# 1_RK3399_PowerPins.net
KiCad netlist of a schematic drawn in Altium Designer
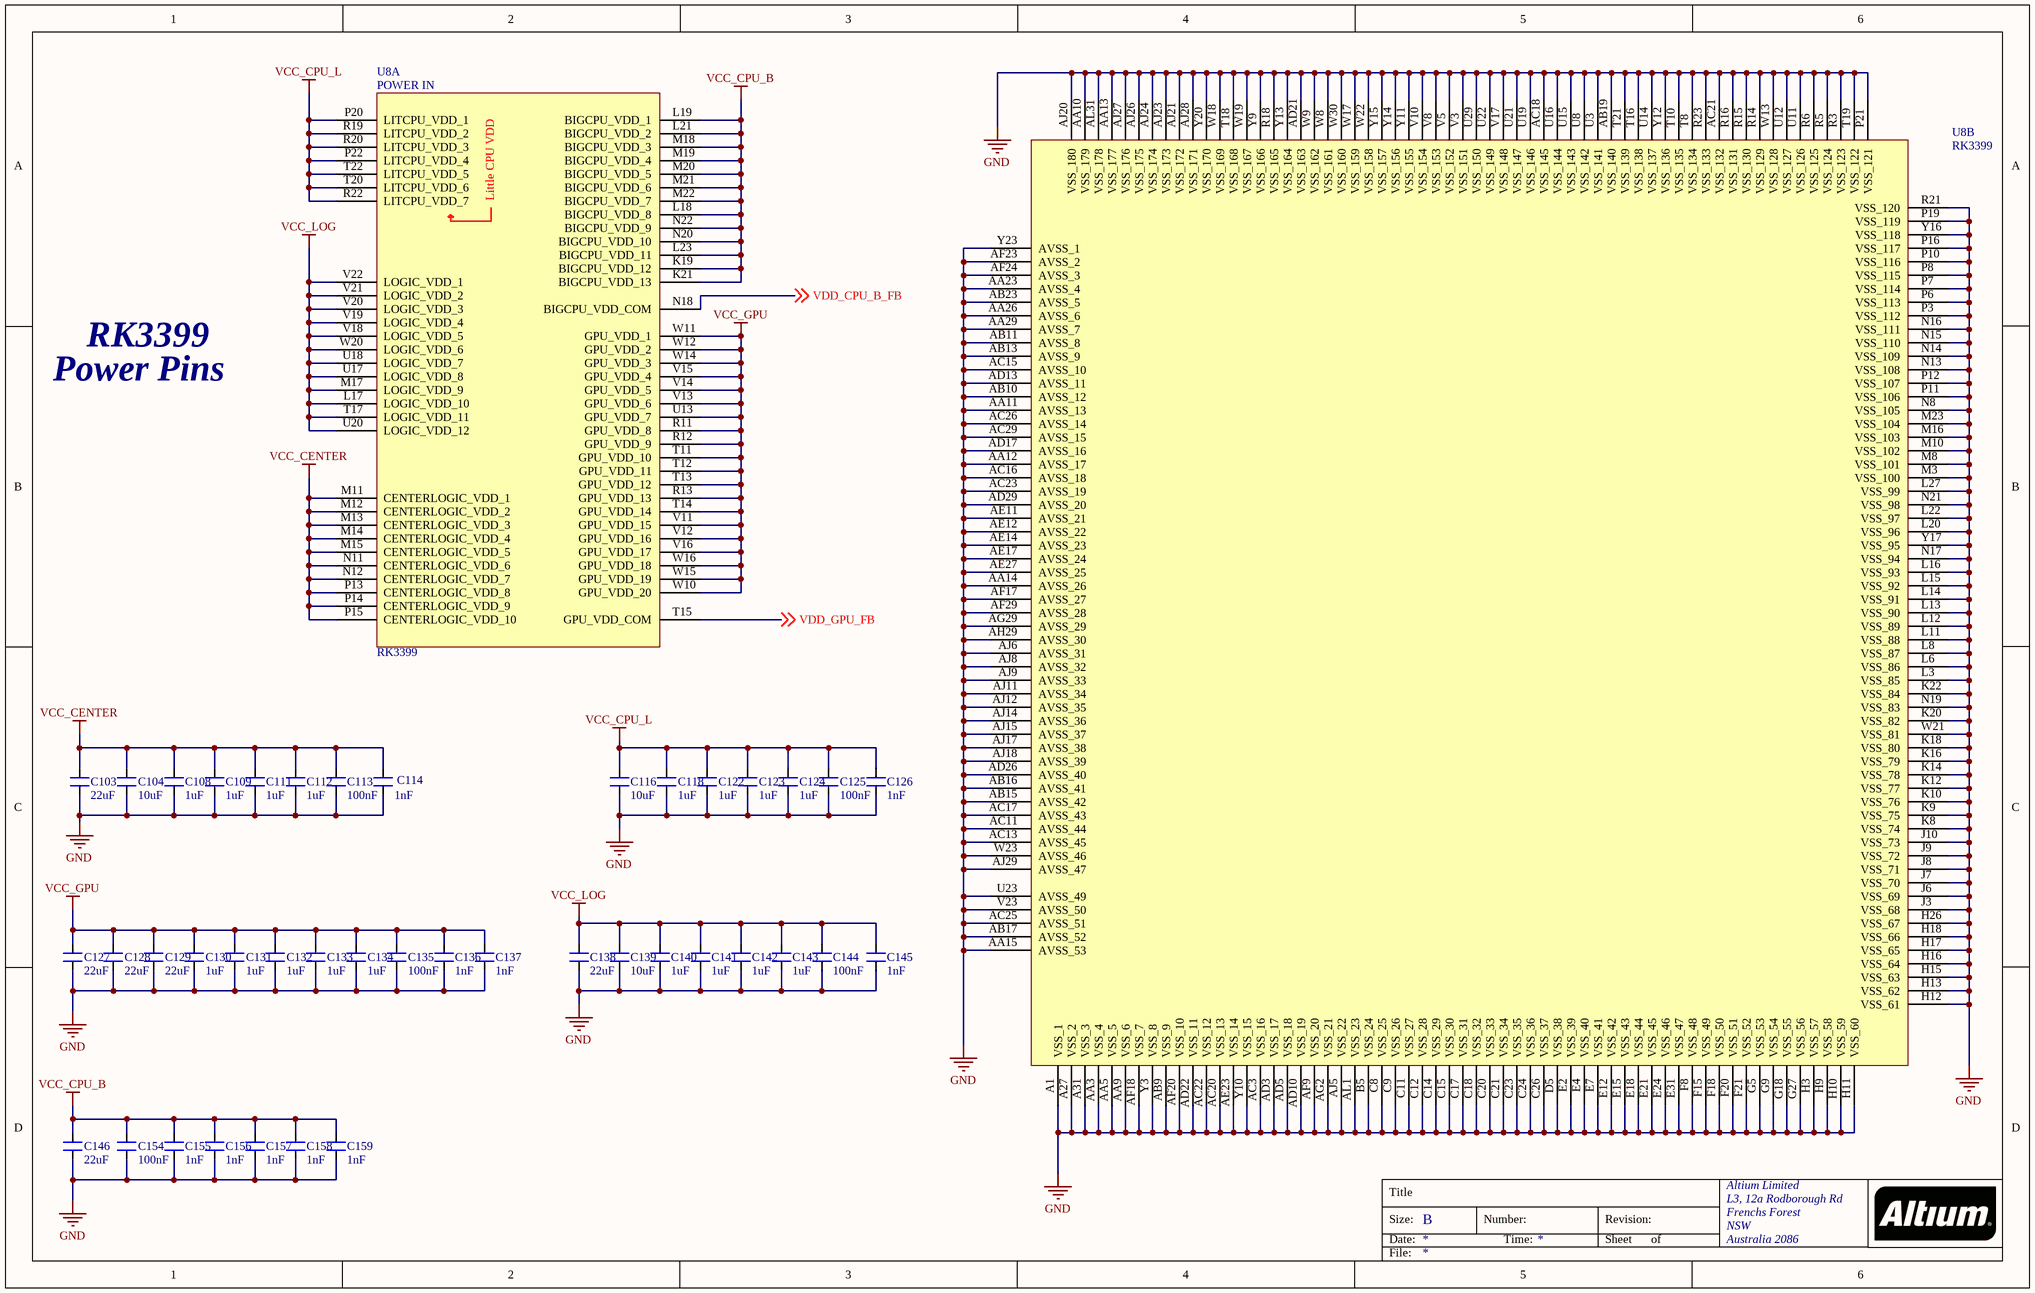
[diagram p0: [1] RK3399_PowerPins.SchDoc]

(export (version "E")
  (design (tool "Eeschema 10.0.6"))
  (components
    (comp (ref "C103")
      (value "22uF")
      (footprint "CAP_0603")
      (description "22µF ±20% 10V Ceramic Capacitor X5R 0603 (1608 Metric)")
      (fields
        (field (name "MANUFACTURER") "Murata Electronics")
        (field (name "MANUFACTURER PART NUMBER") "GRM188R61A226ME15D")
      )
      (libsource (lib "EsteemPCB_SOM_Course_intlib") (part "CAP_22uF-10V-20%-0603"))
    )
    (comp (ref "C104")
      (value "10uF")
      (footprint "CAP_0603")
      (description "10µF ±10% 25V Ceramic Capacitor X5R 0603 (1608 Metric)")
      (fields
        (field (name "MANUFACTURER") "Murata Electronics")
        (field (name "MANUFACTURER PART NUMBER") "GRM188R61E106KA73D")
      )
      (libsource (lib "EsteemPCB_SOM_Course_intlib") (part "CAP_10uF-25V-10%-0603"))
    )
    (comp (ref "C108")
      (value "1uF")
      (footprint "CAP_0201")
      (description "1µF ±20% 16V Ceramic Capacitor X5R 0201 (0603 Metric)")
      (fields
        (field (name "MANUFACTURER") "Samsung Electro-Mechanics")
        (field (name "MANUFACTURER PART NUMBER") "CL03A105MO3NRNH")
      )
      (libsource (lib "EsteemPCB_SOM_Course_intlib") (part "CAP_1uF-16V-10%-0201"))
    )
    (comp (ref "C109")
      (value "1uF")
      (footprint "CAP_0201")
      (description "1µF ±20% 16V Ceramic Capacitor X5R 0201 (0603 Metric)")
      (fields
        (field (name "MANUFACTURER") "Samsung Electro-Mechanics")
        (field (name "MANUFACTURER PART NUMBER") "CL03A105MO3NRNH")
      )
      (libsource (lib "EsteemPCB_SOM_Course_intlib") (part "CAP_1uF-16V-10%-0201"))
    )
    (comp (ref "C111")
      (value "1uF")
      (footprint "CAP_0201")
      (description "1µF ±20% 16V Ceramic Capacitor X5R 0201 (0603 Metric)")
      (fields
        (field (name "MANUFACTURER") "Samsung Electro-Mechanics")
        (field (name "MANUFACTURER PART NUMBER") "CL03A105MO3NRNH")
      )
      (libsource (lib "EsteemPCB_SOM_Course_intlib") (part "CAP_1uF-16V-10%-0201"))
    )
    (comp (ref "C112")
      (value "1uF")
      (footprint "CAP_0201")
      (description "1µF ±20% 16V Ceramic Capacitor X5R 0201 (0603 Metric)")
      (fields
        (field (name "MANUFACTURER") "Samsung Electro-Mechanics")
        (field (name "MANUFACTURER PART NUMBER") "CL03A105MO3NRNH")
      )
      (libsource (lib "EsteemPCB_SOM_Course_intlib") (part "CAP_1uF-16V-10%-0201"))
    )
    (comp (ref "C113")
      (value "100nF")
      (footprint "CAP_0201")
      (description "0.1µF ±10% 25V Ceramic Capacitor X5R 0201 (0603 Metric)")
      (fields
        (field (name "MANUFACTURER") "TDK Corporation")
        (field (name "MANUFACTURER PART NUMBER") "C0603X5R1E104K030BB")
      )
      (libsource (lib "EsteemPCB_SOM_Course_intlib") (part "CAP_100nF-25V-10%-0201"))
    )
    (comp (ref "C114")
      (value "1nF")
      (footprint "CAP_0201")
      (description "1000pF ±10% 16V Ceramic Capacitor X7R 0201 (0603 Metric)")
      (fields
        (field (name "MANUFACTURER") "Murata Electronics")
        (field (name "MANUFACTURER PART NUMBER") "GRM033R71C102KA01D")
      )
      (libsource (lib "EsteemPCB_SOM_Course_intlib") (part "CAP_1nF-16V-10%-0201"))
    )
    (comp (ref "C116")
      (value "10uF")
      (footprint "CAP_0603")
      (description "10µF ±10% 25V Ceramic Capacitor X5R 0603 (1608 Metric)")
      (fields
        (field (name "MANUFACTURER") "Murata Electronics")
        (field (name "MANUFACTURER PART NUMBER") "GRM188R61E106KA73D")
      )
      (libsource (lib "EsteemPCB_SOM_Course_intlib") (part "CAP_10uF-25V-10%-0603"))
    )
    (comp (ref "C118")
      (value "1uF")
      (footprint "CAP_0201")
      (description "1µF ±20% 16V Ceramic Capacitor X5R 0201 (0603 Metric)")
      (fields
        (field (name "MANUFACTURER") "Samsung Electro-Mechanics")
        (field (name "MANUFACTURER PART NUMBER") "CL03A105MO3NRNH")
      )
      (libsource (lib "EsteemPCB_SOM_Course_intlib") (part "CAP_1uF-16V-10%-0201"))
    )
    (comp (ref "C122")
      (value "1uF")
      (footprint "CAP_0201")
      (description "1µF ±20% 16V Ceramic Capacitor X5R 0201 (0603 Metric)")
      (fields
        (field (name "MANUFACTURER") "Samsung Electro-Mechanics")
        (field (name "MANUFACTURER PART NUMBER") "CL03A105MO3NRNH")
      )
      (libsource (lib "EsteemPCB_SOM_Course_intlib") (part "CAP_1uF-16V-10%-0201"))
    )
    (comp (ref "C123")
      (value "1uF")
      (footprint "CAP_0201")
      (description "1µF ±20% 16V Ceramic Capacitor X5R 0201 (0603 Metric)")
      (fields
        (field (name "MANUFACTURER") "Samsung Electro-Mechanics")
        (field (name "MANUFACTURER PART NUMBER") "CL03A105MO3NRNH")
      )
      (libsource (lib "EsteemPCB_SOM_Course_intlib") (part "CAP_1uF-16V-10%-0201"))
    )
    (comp (ref "C124")
      (value "1uF")
      (footprint "CAP_0201")
      (description "1µF ±20% 16V Ceramic Capacitor X5R 0201 (0603 Metric)")
      (fields
        (field (name "MANUFACTURER") "Samsung Electro-Mechanics")
        (field (name "MANUFACTURER PART NUMBER") "CL03A105MO3NRNH")
      )
      (libsource (lib "EsteemPCB_SOM_Course_intlib") (part "CAP_1uF-16V-10%-0201"))
    )
    (comp (ref "C125")
      (value "100nF")
      (footprint "CAP_0201")
      (description "0.1µF ±10% 25V Ceramic Capacitor X5R 0201 (0603 Metric)")
      (fields
        (field (name "MANUFACTURER") "TDK Corporation")
        (field (name "MANUFACTURER PART NUMBER") "C0603X5R1E104K030BB")
      )
      (libsource (lib "EsteemPCB_SOM_Course_intlib") (part "CAP_100nF-25V-10%-0201"))
    )
    (comp (ref "C126")
      (value "1nF")
      (footprint "CAP_0201")
      (description "1000pF ±10% 16V Ceramic Capacitor X7R 0201 (0603 Metric)")
      (fields
        (field (name "MANUFACTURER") "Murata Electronics")
        (field (name "MANUFACTURER PART NUMBER") "GRM033R71C102KA01D")
      )
      (libsource (lib "EsteemPCB_SOM_Course_intlib") (part "CAP_1nF-16V-10%-0201"))
    )
    (comp (ref "C127")
      (value "22uF")
      (footprint "CAP_0603")
      (description "22µF ±20% 10V Ceramic Capacitor X5R 0603 (1608 Metric)")
      (fields
        (field (name "MANUFACTURER") "Murata Electronics")
        (field (name "MANUFACTURER PART NUMBER") "GRM188R61A226ME15D")
      )
      (libsource (lib "EsteemPCB_SOM_Course_intlib") (part "CAP_22uF-10V-20%-0603"))
    )
    (comp (ref "C128")
      (value "22uF")
      (footprint "CAP_0603")
      (description "22µF ±20% 10V Ceramic Capacitor X5R 0603 (1608 Metric)")
      (fields
        (field (name "MANUFACTURER") "Murata Electronics")
        (field (name "MANUFACTURER PART NUMBER") "GRM188R61A226ME15D")
      )
      (libsource (lib "EsteemPCB_SOM_Course_intlib") (part "CAP_22uF-10V-20%-0603"))
    )
    (comp (ref "C129")
      (value "22uF")
      (footprint "CAP_0603")
      (description "22µF ±20% 10V Ceramic Capacitor X5R 0603 (1608 Metric)")
      (fields
        (field (name "MANUFACTURER") "Murata Electronics")
        (field (name "MANUFACTURER PART NUMBER") "GRM188R61A226ME15D")
      )
      (libsource (lib "EsteemPCB_SOM_Course_intlib") (part "CAP_22uF-10V-20%-0603"))
    )
    (comp (ref "C130")
      (value "1uF")
      (footprint "CAP_0201")
      (description "1µF ±20% 16V Ceramic Capacitor X5R 0201 (0603 Metric)")
      (fields
        (field (name "MANUFACTURER") "Samsung Electro-Mechanics")
        (field (name "MANUFACTURER PART NUMBER") "CL03A105MO3NRNH")
      )
      (libsource (lib "EsteemPCB_SOM_Course_intlib") (part "CAP_1uF-16V-10%-0201"))
    )
    (comp (ref "C131")
      (value "1uF")
      (footprint "CAP_0201")
      (description "1µF ±20% 16V Ceramic Capacitor X5R 0201 (0603 Metric)")
      (fields
        (field (name "MANUFACTURER") "Samsung Electro-Mechanics")
        (field (name "MANUFACTURER PART NUMBER") "CL03A105MO3NRNH")
      )
      (libsource (lib "EsteemPCB_SOM_Course_intlib") (part "CAP_1uF-16V-10%-0201"))
    )
    (comp (ref "C132")
      (value "1uF")
      (footprint "CAP_0201")
      (description "1µF ±20% 16V Ceramic Capacitor X5R 0201 (0603 Metric)")
      (fields
        (field (name "MANUFACTURER") "Samsung Electro-Mechanics")
        (field (name "MANUFACTURER PART NUMBER") "CL03A105MO3NRNH")
      )
      (libsource (lib "EsteemPCB_SOM_Course_intlib") (part "CAP_1uF-16V-10%-0201"))
    )
    (comp (ref "C133")
      (value "1uF")
      (footprint "CAP_0201")
      (description "1µF ±20% 16V Ceramic Capacitor X5R 0201 (0603 Metric)")
      (fields
        (field (name "MANUFACTURER") "Samsung Electro-Mechanics")
        (field (name "MANUFACTURER PART NUMBER") "CL03A105MO3NRNH")
      )
      (libsource (lib "EsteemPCB_SOM_Course_intlib") (part "CAP_1uF-16V-10%-0201"))
    )
    (comp (ref "C134")
      (value "1uF")
      (footprint "CAP_0201")
      (description "1µF ±20% 16V Ceramic Capacitor X5R 0201 (0603 Metric)")
      (fields
        (field (name "MANUFACTURER") "Samsung Electro-Mechanics")
        (field (name "MANUFACTURER PART NUMBER") "CL03A105MO3NRNH")
      )
      (libsource (lib "EsteemPCB_SOM_Course_intlib") (part "CAP_1uF-16V-10%-0201"))
    )
    (comp (ref "C135")
      (value "100nF")
      (footprint "CAP_0201")
      (description "0.1µF ±10% 25V Ceramic Capacitor X5R 0201 (0603 Metric)")
      (fields
        (field (name "MANUFACTURER") "TDK Corporation")
        (field (name "MANUFACTURER PART NUMBER") "C0603X5R1E104K030BB")
      )
      (libsource (lib "EsteemPCB_SOM_Course_intlib") (part "CAP_100nF-25V-10%-0201"))
    )
    (comp (ref "C136")
      (value "1nF")
      (footprint "CAP_0201")
      (description "1000pF ±10% 16V Ceramic Capacitor X7R 0201 (0603 Metric)")
      (fields
        (field (name "MANUFACTURER") "Murata Electronics")
        (field (name "MANUFACTURER PART NUMBER") "GRM033R71C102KA01D")
      )
      (libsource (lib "EsteemPCB_SOM_Course_intlib") (part "CAP_1nF-16V-10%-0201"))
    )
    (comp (ref "C137")
      (value "1nF")
      (footprint "CAP_0201")
      (description "1000pF ±10% 16V Ceramic Capacitor X7R 0201 (0603 Metric)")
      (fields
        (field (name "MANUFACTURER") "Murata Electronics")
        (field (name "MANUFACTURER PART NUMBER") "GRM033R71C102KA01D")
      )
      (libsource (lib "EsteemPCB_SOM_Course_intlib") (part "CAP_1nF-16V-10%-0201"))
    )
    (comp (ref "C138")
      (value "22uF")
      (footprint "CAP_0603")
      (description "22µF ±20% 10V Ceramic Capacitor X5R 0603 (1608 Metric)")
      (fields
        (field (name "MANUFACTURER") "Murata Electronics")
        (field (name "MANUFACTURER PART NUMBER") "GRM188R61A226ME15D")
      )
      (libsource (lib "EsteemPCB_SOM_Course_intlib") (part "CAP_22uF-10V-20%-0603"))
    )
    (comp (ref "C139")
      (value "10uF")
      (footprint "CAP_0603")
      (description "10µF ±10% 25V Ceramic Capacitor X5R 0603 (1608 Metric)")
      (fields
        (field (name "MANUFACTURER") "Murata Electronics")
        (field (name "MANUFACTURER PART NUMBER") "GRM188R61E106KA73D")
      )
      (libsource (lib "EsteemPCB_SOM_Course_intlib") (part "CAP_10uF-25V-10%-0603"))
    )
    (comp (ref "C140")
      (value "1uF")
      (footprint "CAP_0201")
      (description "1µF ±20% 16V Ceramic Capacitor X5R 0201 (0603 Metric)")
      (fields
        (field (name "MANUFACTURER") "Samsung Electro-Mechanics")
        (field (name "MANUFACTURER PART NUMBER") "CL03A105MO3NRNH")
      )
      (libsource (lib "EsteemPCB_SOM_Course_intlib") (part "CAP_1uF-16V-10%-0201"))
    )
    (comp (ref "C141")
      (value "1uF")
      (footprint "CAP_0201")
      (description "1µF ±20% 16V Ceramic Capacitor X5R 0201 (0603 Metric)")
      (fields
        (field (name "MANUFACTURER") "Samsung Electro-Mechanics")
        (field (name "MANUFACTURER PART NUMBER") "CL03A105MO3NRNH")
      )
      (libsource (lib "EsteemPCB_SOM_Course_intlib") (part "CAP_1uF-16V-10%-0201"))
    )
    (comp (ref "C142")
      (value "1uF")
      (footprint "CAP_0201")
      (description "1µF ±20% 16V Ceramic Capacitor X5R 0201 (0603 Metric)")
      (fields
        (field (name "MANUFACTURER") "Samsung Electro-Mechanics")
        (field (name "MANUFACTURER PART NUMBER") "CL03A105MO3NRNH")
      )
      (libsource (lib "EsteemPCB_SOM_Course_intlib") (part "CAP_1uF-16V-10%-0201"))
    )
    (comp (ref "C143")
      (value "1uF")
      (footprint "CAP_0201")
      (description "1µF ±20% 16V Ceramic Capacitor X5R 0201 (0603 Metric)")
      (fields
        (field (name "MANUFACTURER") "Samsung Electro-Mechanics")
        (field (name "MANUFACTURER PART NUMBER") "CL03A105MO3NRNH")
      )
      (libsource (lib "EsteemPCB_SOM_Course_intlib") (part "CAP_1uF-16V-10%-0201"))
    )
    (comp (ref "C144")
      (value "100nF")
      (footprint "CAP_0201")
      (description "0.1µF ±10% 25V Ceramic Capacitor X5R 0201 (0603 Metric)")
      (fields
        (field (name "MANUFACTURER") "TDK Corporation")
        (field (name "MANUFACTURER PART NUMBER") "C0603X5R1E104K030BB")
      )
      (libsource (lib "EsteemPCB_SOM_Course_intlib") (part "CAP_100nF-25V-10%-0201"))
    )
    (comp (ref "C145")
      (value "1nF")
      (footprint "CAP_0201")
      (description "1000pF ±10% 16V Ceramic Capacitor X7R 0201 (0603 Metric)")
      (fields
        (field (name "MANUFACTURER") "Murata Electronics")
        (field (name "MANUFACTURER PART NUMBER") "GRM033R71C102KA01D")
      )
      (libsource (lib "EsteemPCB_SOM_Course_intlib") (part "CAP_1nF-16V-10%-0201"))
    )
    (comp (ref "C146")
      (value "22uF")
      (footprint "CAP_0603")
      (description "22µF ±20% 10V Ceramic Capacitor X5R 0603 (1608 Metric)")
      (fields
        (field (name "MANUFACTURER") "Murata Electronics")
        (field (name "MANUFACTURER PART NUMBER") "GRM188R61A226ME15D")
      )
      (libsource (lib "EsteemPCB_SOM_Course_intlib") (part "CAP_22uF-10V-20%-0603"))
    )
    (comp (ref "C154")
      (value "100nF")
      (footprint "CAP_0201")
      (description "0.1µF ±10% 25V Ceramic Capacitor X5R 0201 (0603 Metric)")
      (fields
        (field (name "MANUFACTURER") "TDK Corporation")
        (field (name "MANUFACTURER PART NUMBER") "C0603X5R1E104K030BB")
      )
      (libsource (lib "EsteemPCB_SOM_Course_intlib") (part "CAP_100nF-25V-10%-0201"))
    )
    (comp (ref "C155")
      (value "1nF")
      (footprint "CAP_0201")
      (description "1000pF ±10% 16V Ceramic Capacitor X7R 0201 (0603 Metric)")
      (fields
        (field (name "MANUFACTURER") "Murata Electronics")
        (field (name "MANUFACTURER PART NUMBER") "GRM033R71C102KA01D")
      )
      (libsource (lib "EsteemPCB_SOM_Course_intlib") (part "CAP_1nF-16V-10%-0201"))
    )
    (comp (ref "C156")
      (value "1nF")
      (footprint "CAP_0201")
      (description "1000pF ±10% 16V Ceramic Capacitor X7R 0201 (0603 Metric)")
      (fields
        (field (name "MANUFACTURER") "Murata Electronics")
        (field (name "MANUFACTURER PART NUMBER") "GRM033R71C102KA01D")
      )
      (libsource (lib "EsteemPCB_SOM_Course_intlib") (part "CAP_1nF-16V-10%-0201"))
    )
    (comp (ref "C157")
      (value "1nF")
      (footprint "CAP_0201")
      (description "1000pF ±10% 16V Ceramic Capacitor X7R 0201 (0603 Metric)")
      (fields
        (field (name "MANUFACTURER") "Murata Electronics")
        (field (name "MANUFACTURER PART NUMBER") "GRM033R71C102KA01D")
      )
      (libsource (lib "EsteemPCB_SOM_Course_intlib") (part "CAP_1nF-16V-10%-0201"))
    )
    (comp (ref "C158")
      (value "1nF")
      (footprint "CAP_0201")
      (description "1000pF ±10% 16V Ceramic Capacitor X7R 0201 (0603 Metric)")
      (fields
        (field (name "MANUFACTURER") "Murata Electronics")
        (field (name "MANUFACTURER PART NUMBER") "GRM033R71C102KA01D")
      )
      (libsource (lib "EsteemPCB_SOM_Course_intlib") (part "CAP_1nF-16V-10%-0201"))
    )
    (comp (ref "C159")
      (value "1nF")
      (footprint "CAP_0201")
      (description "1000pF ±10% 16V Ceramic Capacitor X7R 0201 (0603 Metric)")
      (fields
        (field (name "MANUFACTURER") "Murata Electronics")
        (field (name "MANUFACTURER PART NUMBER") "GRM033R71C102KA01D")
      )
      (libsource (lib "EsteemPCB_SOM_Course_intlib") (part "CAP_1nF-16V-10%-0201"))
    )
    (comp (ref "U8")
      (value "RK3399")
      (footprint "FBGA828_23_826X826")
      (description "RK3399 is a low power, high performance processor for computing, personal mobile.")
      (fields (field (name "MANUFACTURER") "Rockchip"))
      (libsource (lib "EsteemPCB_SOM_Course_intlib") (part "IC_RK3399-FCBGA828"))
    )
  )
  (nets
    (net (code "1") (name "GND") (class "Default")
      (node (ref "C103") (pin "1") (pinfunction "1_1") (pintype "passive"))
      (node (ref "C104") (pin "1") (pinfunction "1_1") (pintype "passive"))
      (node (ref "C108") (pin "1") (pinfunction "1_1") (pintype "passive"))
      (node (ref "C109") (pin "1") (pinfunction "1_1") (pintype "passive"))
      (node (ref "C111") (pin "1") (pinfunction "1_1") (pintype "passive"))
      (node (ref "C112") (pin "1") (pinfunction "1_1") (pintype "passive"))
      (node (ref "C113") (pin "1") (pinfunction "1_1") (pintype "passive"))
      (node (ref "C114") (pin "1") (pinfunction "1_1") (pintype "passive"))
      (node (ref "C116") (pin "1") (pinfunction "1_1") (pintype "passive"))
      (node (ref "C118") (pin "1") (pinfunction "1_1") (pintype "passive"))
      (node (ref "C122") (pin "1") (pinfunction "1_1") (pintype "passive"))
      (node (ref "C123") (pin "1") (pinfunction "1_1") (pintype "passive"))
      (node (ref "C124") (pin "1") (pinfunction "1_1") (pintype "passive"))
      (node (ref "C125") (pin "1") (pinfunction "1_1") (pintype "passive"))
      (node (ref "C126") (pin "1") (pinfunction "1_1") (pintype "passive"))
      (node (ref "C127") (pin "1") (pinfunction "1_1") (pintype "passive"))
      (node (ref "C128") (pin "1") (pinfunction "1_1") (pintype "passive"))
      (node (ref "C129") (pin "1") (pinfunction "1_1") (pintype "passive"))
      (node (ref "C130") (pin "1") (pinfunction "1_1") (pintype "passive"))
      (node (ref "C131") (pin "1") (pinfunction "1_1") (pintype "passive"))
      (node (ref "C132") (pin "1") (pinfunction "1_1") (pintype "passive"))
      (node (ref "C133") (pin "1") (pinfunction "1_1") (pintype "passive"))
      (node (ref "C134") (pin "1") (pinfunction "1_1") (pintype "passive"))
      (node (ref "C135") (pin "1") (pinfunction "1_1") (pintype "passive"))
      (node (ref "C136") (pin "1") (pinfunction "1_1") (pintype "passive"))
      (node (ref "C137") (pin "1") (pinfunction "1_1") (pintype "passive"))
      (node (ref "C138") (pin "1") (pinfunction "1_1") (pintype "passive"))
      (node (ref "C139") (pin "1") (pinfunction "1_1") (pintype "passive"))
      (node (ref "C140") (pin "1") (pinfunction "1_1") (pintype "passive"))
      (node (ref "C141") (pin "1") (pinfunction "1_1") (pintype "passive"))
      (node (ref "C142") (pin "1") (pinfunction "1_1") (pintype "passive"))
      (node (ref "C143") (pin "1") (pinfunction "1_1") (pintype "passive"))
      (node (ref "C144") (pin "1") (pinfunction "1_1") (pintype "passive"))
      (node (ref "C145") (pin "1") (pinfunction "1_1") (pintype "passive"))
      (node (ref "C146") (pin "1") (pinfunction "1_1") (pintype "passive"))
      (node (ref "C154") (pin "1") (pinfunction "1_1") (pintype "passive"))
      (node (ref "C155") (pin "1") (pinfunction "1_1") (pintype "passive"))
      (node (ref "C156") (pin "1") (pinfunction "1_1") (pintype "passive"))
      (node (ref "C157") (pin "1") (pinfunction "1_1") (pintype "passive"))
      (node (ref "C158") (pin "1") (pinfunction "1_1") (pintype "passive"))
      (node (ref "C159") (pin "1") (pinfunction "1_1") (pintype "passive"))
      (node (ref "U8") (pin "A1") (pinfunction "VSS_1_A1") (pintype "passive"))
      (node (ref "U8") (pin "A27") (pinfunction "VSS_2_A27") (pintype "passive"))
      (node (ref "U8") (pin "A31") (pinfunction "VSS_3_A31") (pintype "passive"))
      (node (ref "U8") (pin "AA10") (pinfunction "VSS_179_AA10") (pintype "passive"))
      (node (ref "U8") (pin "AA11") (pinfunction "AVSS_13_AA11") (pintype "passive"))
      (node (ref "U8") (pin "AA12") (pinfunction "AVSS_17_AA12") (pintype "passive"))
      (node (ref "U8") (pin "AA13") (pinfunction "VSS_177_AA13") (pintype "passive"))
      (node (ref "U8") (pin "AA14") (pinfunction "AVSS_26_AA14") (pintype "passive"))
      (node (ref "U8") (pin "AA15") (pinfunction "AVSS_53_AA15") (pintype "passive"))
      (node (ref "U8") (pin "AA23") (pinfunction "AVSS_4_AA23") (pintype "passive"))
      (node (ref "U8") (pin "AA26") (pinfunction "AVSS_6_AA26") (pintype "passive"))
      (node (ref "U8") (pin "AA29") (pinfunction "AVSS_7_AA29") (pintype "passive"))
      (node (ref "U8") (pin "AA3") (pinfunction "VSS_4_AA3") (pintype "passive"))
      (node (ref "U8") (pin "AA5") (pinfunction "VSS_5_AA5") (pintype "passive"))
      (node (ref "U8") (pin "AA9") (pinfunction "VSS_6_AA9") (pintype "passive"))
      (node (ref "U8") (pin "AB10") (pinfunction "AVSS_12_AB10") (pintype "passive"))
      (node (ref "U8") (pin "AB11") (pinfunction "AVSS_8_AB11") (pintype "passive"))
      (node (ref "U8") (pin "AB13") (pinfunction "AVSS_9_AB13") (pintype "passive"))
      (node (ref "U8") (pin "AB15") (pinfunction "AVSS_42_AB15") (pintype "passive"))
      (node (ref "U8") (pin "AB16") (pinfunction "AVSS_41_AB16") (pintype "passive"))
      (node (ref "U8") (pin "AB17") (pinfunction "AVSS_52_AB17") (pintype "passive"))
      (node (ref "U8") (pin "AB19") (pinfunction "VSS_140_AB19") (pintype "passive"))
      (node (ref "U8") (pin "AB23") (pinfunction "AVSS_5_AB23") (pintype "passive"))
      (node (ref "U8") (pin "AB9") (pinfunction "VSS_9_AB9") (pintype "passive"))
      (node (ref "U8") (pin "AC11") (pinfunction "AVSS_44_AC11") (pintype "passive"))
      (node (ref "U8") (pin "AC13") (pinfunction "AVSS_45_AC13") (pintype "passive"))
      (node (ref "U8") (pin "AC15") (pinfunction "AVSS_10_AC15") (pintype "passive"))
      (node (ref "U8") (pin "AC16") (pinfunction "AVSS_18_AC16") (pintype "passive"))
      (node (ref "U8") (pin "AC17") (pinfunction "AVSS_43_AC17") (pintype "passive"))
      (node (ref "U8") (pin "AC18") (pinfunction "VSS_145_AC18") (pintype "passive"))
      (node (ref "U8") (pin "AC20") (pinfunction "VSS_13_AC20") (pintype "passive"))
      (node (ref "U8") (pin "AC21") (pinfunction "VSS_132_AC21") (pintype "passive"))
      (node (ref "U8") (pin "AC22") (pinfunction "VSS_12_AC22") (pintype "passive"))
      (node (ref "U8") (pin "AC23") (pinfunction "AVSS_19_AC23") (pintype "passive"))
      (node (ref "U8") (pin "AC25") (pinfunction "AVSS_51_AC25") (pintype "passive"))
      (node (ref "U8") (pin "AC26") (pinfunction "AVSS_14_AC26") (pintype "passive"))
      (node (ref "U8") (pin "AC29") (pinfunction "AVSS_15_AC29") (pintype "passive"))
      (node (ref "U8") (pin "AC3") (pinfunction "VSS_16_AC3") (pintype "passive"))
      (node (ref "U8") (pin "AD10") (pinfunction "VSS_19_AD10") (pintype "passive"))
      (node (ref "U8") (pin "AD13") (pinfunction "AVSS_11_AD13") (pintype "passive"))
      (node (ref "U8") (pin "AD17") (pinfunction "AVSS_16_AD17") (pintype "passive"))
      (node (ref "U8") (pin "AD21") (pinfunction "VSS_163_AD21") (pintype "passive"))
      (node (ref "U8") (pin "AD22") (pinfunction "VSS_11_AD22") (pintype "passive"))
      (node (ref "U8") (pin "AD26") (pinfunction "AVSS_40_AD26") (pintype "passive"))
      (node (ref "U8") (pin "AD29") (pinfunction "AVSS_20_AD29") (pintype "passive"))
      (node (ref "U8") (pin "AD3") (pinfunction "VSS_17_AD3") (pintype "passive"))
      (node (ref "U8") (pin "AD5") (pinfunction "VSS_18_AD5") (pintype "passive"))
      (node (ref "U8") (pin "AE11") (pinfunction "AVSS_21_AE11") (pintype "passive"))
      (node (ref "U8") (pin "AE12") (pinfunction "AVSS_22_AE12") (pintype "passive"))
      (node (ref "U8") (pin "AE14") (pinfunction "AVSS_23_AE14") (pintype "passive"))
      (node (ref "U8") (pin "AE17") (pinfunction "AVSS_24_AE17") (pintype "passive"))
      (node (ref "U8") (pin "AE23") (pinfunction "VSS_14_AE23") (pintype "passive"))
      (node (ref "U8") (pin "AE27") (pinfunction "AVSS_25_AE27") (pintype "passive"))
      (node (ref "U8") (pin "AF17") (pinfunction "AVSS_27_AF17") (pintype "passive"))
      (node (ref "U8") (pin "AF18") (pinfunction "VSS_7_AF18") (pintype "passive"))
      (node (ref "U8") (pin "AF20") (pinfunction "VSS_10_AF20") (pintype "passive"))
      (node (ref "U8") (pin "AF23") (pinfunction "AVSS_2_AF23") (pintype "passive"))
      (node (ref "U8") (pin "AF24") (pinfunction "AVSS_3_AF24") (pintype "passive"))
      (node (ref "U8") (pin "AF29") (pinfunction "AVSS_28_AF29") (pintype "passive"))
      (node (ref "U8") (pin "AF9") (pinfunction "VSS_20_AF9") (pintype "passive"))
      (node (ref "U8") (pin "AG2") (pinfunction "VSS_21_AG2") (pintype "passive"))
      (node (ref "U8") (pin "AG29") (pinfunction "AVSS_29_AG29") (pintype "passive"))
      (node (ref "U8") (pin "AH29") (pinfunction "AVSS_30_AH29") (pintype "passive"))
      (node (ref "U8") (pin "AJ11") (pinfunction "AVSS_34_AJ11") (pintype "passive"))
      (node (ref "U8") (pin "AJ12") (pinfunction "AVSS_35_AJ12") (pintype "passive"))
      (node (ref "U8") (pin "AJ14") (pinfunction "AVSS_36_AJ14") (pintype "passive"))
      (node (ref "U8") (pin "AJ15") (pinfunction "AVSS_37_AJ15") (pintype "passive"))
      (node (ref "U8") (pin "AJ17") (pinfunction "AVSS_38_AJ17") (pintype "passive"))
      (node (ref "U8") (pin "AJ18") (pinfunction "AVSS_39_AJ18") (pintype "passive"))
      (node (ref "U8") (pin "AJ20") (pinfunction "VSS_180_AJ20") (pintype "passive"))
      (node (ref "U8") (pin "AJ21") (pinfunction "VSS_172_AJ21") (pintype "passive"))
      (node (ref "U8") (pin "AJ23") (pinfunction "VSS_173_AJ23") (pintype "passive"))
      (node (ref "U8") (pin "AJ24") (pinfunction "VSS_174_AJ24") (pintype "passive"))
      (node (ref "U8") (pin "AJ26") (pinfunction "VSS_175_AJ26") (pintype "passive"))
      (node (ref "U8") (pin "AJ27") (pinfunction "VSS_176_AJ27") (pintype "passive"))
      (node (ref "U8") (pin "AJ28") (pinfunction "VSS_171_AJ28") (pintype "passive"))
      (node (ref "U8") (pin "AJ29") (pinfunction "AVSS_47_AJ29") (pintype "passive"))
      (node (ref "U8") (pin "AJ5") (pinfunction "VSS_22_AJ5") (pintype "passive"))
      (node (ref "U8") (pin "AJ6") (pinfunction "AVSS_31_AJ6") (pintype "passive"))
      (node (ref "U8") (pin "AJ8") (pinfunction "AVSS_32_AJ8") (pintype "passive"))
      (node (ref "U8") (pin "AJ9") (pinfunction "AVSS_33_AJ9") (pintype "passive"))
      (node (ref "U8") (pin "AL1") (pinfunction "VSS_23_AL1") (pintype "passive"))
      (node (ref "U8") (pin "AL31") (pinfunction "VSS_178_AL31") (pintype "passive"))
      (node (ref "U8") (pin "B5") (pinfunction "VSS_24_B5") (pintype "passive"))
      (node (ref "U8") (pin "C11") (pinfunction "VSS_27_C11") (pintype "passive"))
      (node (ref "U8") (pin "C12") (pinfunction "VSS_28_C12") (pintype "passive"))
      (node (ref "U8") (pin "C14") (pinfunction "VSS_29_C14") (pintype "passive"))
      (node (ref "U8") (pin "C15") (pinfunction "VSS_30_C15") (pintype "passive"))
      (node (ref "U8") (pin "C17") (pinfunction "VSS_31_C17") (pintype "passive"))
      (node (ref "U8") (pin "C18") (pinfunction "VSS_32_C18") (pintype "passive"))
      (node (ref "U8") (pin "C20") (pinfunction "VSS_33_C20") (pintype "passive"))
      (node (ref "U8") (pin "C21") (pinfunction "VSS_34_C21") (pintype "passive"))
      (node (ref "U8") (pin "C23") (pinfunction "VSS_35_C23") (pintype "passive"))
      (node (ref "U8") (pin "C24") (pinfunction "VSS_36_C24") (pintype "passive"))
      (node (ref "U8") (pin "C26") (pinfunction "VSS_37_C26") (pintype "passive"))
      (node (ref "U8") (pin "C8") (pinfunction "VSS_25_C8") (pintype "passive"))
      (node (ref "U8") (pin "C9") (pinfunction "VSS_26_C9") (pintype "passive"))
      (node (ref "U8") (pin "D5") (pinfunction "VSS_38_D5") (pintype "passive"))
      (node (ref "U8") (pin "E12") (pinfunction "VSS_42_E12") (pintype "passive"))
      (node (ref "U8") (pin "E15") (pinfunction "VSS_43_E15") (pintype "passive"))
      (node (ref "U8") (pin "E18") (pinfunction "VSS_44_E18") (pintype "passive"))
      (node (ref "U8") (pin "E2") (pinfunction "VSS_39_E2") (pintype "passive"))
      (node (ref "U8") (pin "E21") (pinfunction "VSS_45_E21") (pintype "passive"))
      (node (ref "U8") (pin "E24") (pinfunction "VSS_46_E24") (pintype "passive"))
      (node (ref "U8") (pin "E31") (pinfunction "VSS_47_E31") (pintype "passive"))
      (node (ref "U8") (pin "E4") (pinfunction "VSS_40_E4") (pintype "passive"))
      (node (ref "U8") (pin "E7") (pinfunction "VSS_41_E7") (pintype "passive"))
      (node (ref "U8") (pin "F15") (pinfunction "VSS_49_F15") (pintype "passive"))
      (node (ref "U8") (pin "F18") (pinfunction "VSS_50_F18") (pintype "passive"))
      (node (ref "U8") (pin "F20") (pinfunction "VSS_51_F20") (pintype "passive"))
      (node (ref "U8") (pin "F21") (pinfunction "VSS_52_F21") (pintype "passive"))
      (node (ref "U8") (pin "F8") (pinfunction "VSS_48_F8") (pintype "passive"))
      (node (ref "U8") (pin "G18") (pinfunction "VSS_55_G18") (pintype "passive"))
      (node (ref "U8") (pin "G27") (pinfunction "VSS_56_G27") (pintype "passive"))
      (node (ref "U8") (pin "G5") (pinfunction "VSS_53_G5") (pintype "passive"))
      (node (ref "U8") (pin "G9") (pinfunction "VSS_54_G9") (pintype "passive"))
      (node (ref "U8") (pin "H10") (pinfunction "VSS_59_H10") (pintype "passive"))
      (node (ref "U8") (pin "H11") (pinfunction "VSS_60_H11") (pintype "passive"))
      (node (ref "U8") (pin "H12") (pinfunction "VSS_61_H12") (pintype "passive"))
      (node (ref "U8") (pin "H13") (pinfunction "VSS_62_H13") (pintype "passive"))
      (node (ref "U8") (pin "H15") (pinfunction "VSS_63_H15") (pintype "passive"))
      (node (ref "U8") (pin "H16") (pinfunction "VSS_64_H16") (pintype "passive"))
      (node (ref "U8") (pin "H17") (pinfunction "VSS_65_H17") (pintype "passive"))
      (node (ref "U8") (pin "H18") (pinfunction "VSS_66_H18") (pintype "passive"))
      (node (ref "U8") (pin "H26") (pinfunction "VSS_67_H26") (pintype "passive"))
      (node (ref "U8") (pin "H3") (pinfunction "VSS_57_H3") (pintype "passive"))
      (node (ref "U8") (pin "H9") (pinfunction "VSS_58_H9") (pintype "passive"))
      (node (ref "U8") (pin "J10") (pinfunction "VSS_73_J10") (pintype "passive"))
      (node (ref "U8") (pin "J3") (pinfunction "VSS_68_J3") (pintype "passive"))
      (node (ref "U8") (pin "J6") (pinfunction "VSS_69_J6") (pintype "passive"))
      (node (ref "U8") (pin "J7") (pinfunction "VSS_70_J7") (pintype "passive"))
      (node (ref "U8") (pin "J8") (pinfunction "VSS_71_J8") (pintype "passive"))
      (node (ref "U8") (pin "J9") (pinfunction "VSS_72_J9") (pintype "passive"))
      (node (ref "U8") (pin "K10") (pinfunction "VSS_76_K10") (pintype "passive"))
      (node (ref "U8") (pin "K12") (pinfunction "VSS_77_K12") (pintype "passive"))
      (node (ref "U8") (pin "K14") (pinfunction "VSS_78_K14") (pintype "passive"))
      (node (ref "U8") (pin "K16") (pinfunction "VSS_79_K16") (pintype "passive"))
      (node (ref "U8") (pin "K18") (pinfunction "VSS_80_K18") (pintype "passive"))
      (node (ref "U8") (pin "K20") (pinfunction "VSS_82_K20") (pintype "passive"))
      (node (ref "U8") (pin "K22") (pinfunction "VSS_84_K22") (pintype "passive"))
      (node (ref "U8") (pin "K8") (pinfunction "VSS_74_K8") (pintype "passive"))
      (node (ref "U8") (pin "K9") (pinfunction "VSS_75_K9") (pintype "passive"))
      (node (ref "U8") (pin "L11") (pinfunction "VSS_88_L11") (pintype "passive"))
      (node (ref "U8") (pin "L12") (pinfunction "VSS_89_L12") (pintype "passive"))
      (node (ref "U8") (pin "L13") (pinfunction "VSS_90_L13") (pintype "passive"))
      (node (ref "U8") (pin "L14") (pinfunction "VSS_91_L14") (pintype "passive"))
      (node (ref "U8") (pin "L15") (pinfunction "VSS_92_L15") (pintype "passive"))
      (node (ref "U8") (pin "L16") (pinfunction "VSS_93_L16") (pintype "passive"))
      (node (ref "U8") (pin "L20") (pinfunction "VSS_96_L20") (pintype "passive"))
      (node (ref "U8") (pin "L22") (pinfunction "VSS_97_L22") (pintype "passive"))
      (node (ref "U8") (pin "L27") (pinfunction "VSS_99_L27") (pintype "passive"))
      (node (ref "U8") (pin "L3") (pinfunction "VSS_85_L3") (pintype "passive"))
      (node (ref "U8") (pin "L6") (pinfunction "VSS_86_L6") (pintype "passive"))
      (node (ref "U8") (pin "L8") (pinfunction "VSS_87_L8") (pintype "passive"))
      (node (ref "U8") (pin "M10") (pinfunction "VSS_102_M10") (pintype "passive"))
      (node (ref "U8") (pin "M16") (pinfunction "VSS_103_M16") (pintype "passive"))
      (node (ref "U8") (pin "M23") (pinfunction "VSS_104_M23") (pintype "passive"))
      (node (ref "U8") (pin "M3") (pinfunction "VSS_100_M3") (pintype "passive"))
      (node (ref "U8") (pin "M8") (pinfunction "VSS_101_M8") (pintype "passive"))
      (node (ref "U8") (pin "N13") (pinfunction "VSS_108_N13") (pintype "passive"))
      (node (ref "U8") (pin "N14") (pinfunction "VSS_109_N14") (pintype "passive"))
      (node (ref "U8") (pin "N15") (pinfunction "VSS_110_N15") (pintype "passive"))
      (node (ref "U8") (pin "N16") (pinfunction "VSS_111_N16") (pintype "passive"))
      (node (ref "U8") (pin "N17") (pinfunction "VSS_94_N17") (pintype "passive"))
      (node (ref "U8") (pin "N19") (pinfunction "VSS_83_N19") (pintype "passive"))
      (node (ref "U8") (pin "N21") (pinfunction "VSS_98_N21") (pintype "passive"))
      (node (ref "U8") (pin "N8") (pinfunction "VSS_105_N8") (pintype "passive"))
      (node (ref "U8") (pin "P10") (pinfunction "VSS_116_P10") (pintype "passive"))
      (node (ref "U8") (pin "P11") (pinfunction "VSS_106_P11") (pintype "passive"))
      (node (ref "U8") (pin "P12") (pinfunction "VSS_107_P12") (pintype "passive"))
      (node (ref "U8") (pin "P16") (pinfunction "VSS_117_P16") (pintype "passive"))
      (node (ref "U8") (pin "P19") (pinfunction "VSS_119_P19") (pintype "passive"))
      (node (ref "U8") (pin "P21") (pinfunction "VSS_121_P21") (pintype "passive"))
      (node (ref "U8") (pin "P3") (pinfunction "VSS_112_P3") (pintype "passive"))
      (node (ref "U8") (pin "P6") (pinfunction "VSS_113_P6") (pintype "passive"))
      (node (ref "U8") (pin "P7") (pinfunction "VSS_114_P7") (pintype "passive"))
      (node (ref "U8") (pin "P8") (pinfunction "VSS_115_P8") (pintype "passive"))
      (node (ref "U8") (pin "R14") (pinfunction "VSS_129_R14") (pintype "passive"))
      (node (ref "U8") (pin "R15") (pinfunction "VSS_130_R15") (pintype "passive"))
      (node (ref "U8") (pin "R16") (pinfunction "VSS_131_R16") (pintype "passive"))
      (node (ref "U8") (pin "R18") (pinfunction "VSS_165_R18") (pintype "passive"))
      (node (ref "U8") (pin "R21") (pinfunction "VSS_120_R21") (pintype "passive"))
      (node (ref "U8") (pin "R23") (pinfunction "VSS_133_R23") (pintype "passive"))
      (node (ref "U8") (pin "R3") (pinfunction "VSS_123_R3") (pintype "passive"))
      (node (ref "U8") (pin "R5") (pinfunction "VSS_124_R5") (pintype "passive"))
      (node (ref "U8") (pin "R6") (pinfunction "VSS_125_R6") (pintype "passive"))
      (node (ref "U8") (pin "T10") (pinfunction "VSS_135_T10") (pintype "passive"))
      (node (ref "U8") (pin "T16") (pinfunction "VSS_138_T16") (pintype "passive"))
      (node (ref "U8") (pin "T18") (pinfunction "VSS_168_T18") (pintype "passive"))
      (node (ref "U8") (pin "T19") (pinfunction "VSS_122_T19") (pintype "passive"))
      (node (ref "U8") (pin "T21") (pinfunction "VSS_139_T21") (pintype "passive"))
      (node (ref "U8") (pin "T8") (pinfunction "VSS_134_T8") (pintype "passive"))
      (node (ref "U8") (pin "U11") (pinfunction "VSS_126_U11") (pintype "passive"))
      (node (ref "U8") (pin "U12") (pinfunction "VSS_127_U12") (pintype "passive"))
      (node (ref "U8") (pin "U14") (pinfunction "VSS_137_U14") (pintype "passive"))
      (node (ref "U8") (pin "U15") (pinfunction "VSS_143_U15") (pintype "passive"))
      (node (ref "U8") (pin "U16") (pinfunction "VSS_144_U16") (pintype "passive"))
      (node (ref "U8") (pin "U19") (pinfunction "VSS_146_U19") (pintype "passive"))
      (node (ref "U8") (pin "U21") (pinfunction "VSS_147_U21") (pintype "passive"))
      (node (ref "U8") (pin "U22") (pinfunction "VSS_149_U22") (pintype "passive"))
      (node (ref "U8") (pin "U23") (pinfunction "AVSS_49_U23") (pintype "passive"))
      (node (ref "U8") (pin "U29") (pinfunction "VSS_150_U29") (pintype "passive"))
      (node (ref "U8") (pin "U3") (pinfunction "VSS_141_U3") (pintype "passive"))
      (node (ref "U8") (pin "U8") (pinfunction "VSS_142_U8") (pintype "passive"))
      (node (ref "U8") (pin "V10") (pinfunction "VSS_154_V10") (pintype "passive"))
      (node (ref "U8") (pin "V17") (pinfunction "VSS_148_V17") (pintype "passive"))
      (node (ref "U8") (pin "V23") (pinfunction "AVSS_50_V23") (pintype "passive"))
      (node (ref "U8") (pin "V3") (pinfunction "VSS_151_V3") (pintype "passive"))
      (node (ref "U8") (pin "V5") (pinfunction "VSS_152_V5") (pintype "passive"))
      (node (ref "U8") (pin "V8") (pinfunction "VSS_153_V8") (pintype "passive"))
      (node (ref "U8") (pin "W13") (pinfunction "VSS_128_W13") (pintype "passive"))
      (node (ref "U8") (pin "W17") (pinfunction "VSS_159_W17") (pintype "passive"))
      (node (ref "U8") (pin "W18") (pinfunction "VSS_169_W18") (pintype "passive"))
      (node (ref "U8") (pin "W19") (pinfunction "VSS_167_W19") (pintype "passive"))
      (node (ref "U8") (pin "W21") (pinfunction "VSS_81_W21") (pintype "passive"))
      (node (ref "U8") (pin "W22") (pinfunction "VSS_158_W22") (pintype "passive"))
      (node (ref "U8") (pin "W23") (pinfunction "AVSS_46_W23") (pintype "passive"))
      (node (ref "U8") (pin "W30") (pinfunction "VSS_160_W30") (pintype "passive"))
      (node (ref "U8") (pin "W8") (pinfunction "VSS_161_W8") (pintype "passive"))
      (node (ref "U8") (pin "W9") (pinfunction "VSS_162_W9") (pintype "passive"))
      (node (ref "U8") (pin "Y10") (pinfunction "VSS_15_Y10") (pintype "passive"))
      (node (ref "U8") (pin "Y11") (pinfunction "VSS_155_Y11") (pintype "passive"))
      (node (ref "U8") (pin "Y12") (pinfunction "VSS_136_Y12") (pintype "passive"))
      (node (ref "U8") (pin "Y13") (pinfunction "VSS_164_Y13") (pintype "passive"))
      (node (ref "U8") (pin "Y14") (pinfunction "VSS_156_Y14") (pintype "passive"))
      (node (ref "U8") (pin "Y15") (pinfunction "VSS_157_Y15") (pintype "passive"))
      (node (ref "U8") (pin "Y16") (pinfunction "VSS_118_Y16") (pintype "passive"))
      (node (ref "U8") (pin "Y17") (pinfunction "VSS_95_Y17") (pintype "passive"))
      (node (ref "U8") (pin "Y20") (pinfunction "VSS_170_Y20") (pintype "passive"))
      (node (ref "U8") (pin "Y23") (pinfunction "AVSS_1_Y23") (pintype "passive"))
      (node (ref "U8") (pin "Y3") (pinfunction "VSS_8_Y3") (pintype "passive"))
      (node (ref "U8") (pin "Y9") (pinfunction "VSS_166_Y9") (pintype "passive"))
    )
    (net (code "2") (name "VCC_CENTER") (class "Default")
      (node (ref "C103") (pin "2") (pinfunction "2_2") (pintype "passive"))
      (node (ref "C104") (pin "2") (pinfunction "2_2") (pintype "passive"))
      (node (ref "C108") (pin "2") (pinfunction "2_2") (pintype "passive"))
      (node (ref "C109") (pin "2") (pinfunction "2_2") (pintype "passive"))
      (node (ref "C111") (pin "2") (pinfunction "2_2") (pintype "passive"))
      (node (ref "C112") (pin "2") (pinfunction "2_2") (pintype "passive"))
      (node (ref "C113") (pin "2") (pinfunction "2_2") (pintype "passive"))
      (node (ref "C114") (pin "2") (pinfunction "2_2") (pintype "passive"))
      (node (ref "U8") (pin "M11") (pinfunction "CENTERLOGIC_VDD_1_M11") (pintype "passive"))
      (node (ref "U8") (pin "M12") (pinfunction "CENTERLOGIC_VDD_2_M12") (pintype "passive"))
      (node (ref "U8") (pin "M13") (pinfunction "CENTERLOGIC_VDD_3_M13") (pintype "passive"))
      (node (ref "U8") (pin "M14") (pinfunction "CENTERLOGIC_VDD_4_M14") (pintype "passive"))
      (node (ref "U8") (pin "M15") (pinfunction "CENTERLOGIC_VDD_5_M15") (pintype "passive"))
      (node (ref "U8") (pin "N11") (pinfunction "CENTERLOGIC_VDD_6_N11") (pintype "passive"))
      (node (ref "U8") (pin "N12") (pinfunction "CENTERLOGIC_VDD_7_N12") (pintype "passive"))
      (node (ref "U8") (pin "P13") (pinfunction "CENTERLOGIC_VDD_8_P13") (pintype "passive"))
      (node (ref "U8") (pin "P14") (pinfunction "CENTERLOGIC_VDD_9_P14") (pintype "passive"))
      (node (ref "U8") (pin "P15") (pinfunction "CENTERLOGIC_VDD_10_P15") (pintype "passive"))
    )
    (net (code "3") (name "VCC_CPU_B") (class "Default")
      (node (ref "C146") (pin "2") (pinfunction "2_2") (pintype "passive"))
      (node (ref "C154") (pin "2") (pinfunction "2_2") (pintype "passive"))
      (node (ref "C155") (pin "2") (pinfunction "2_2") (pintype "passive"))
      (node (ref "C156") (pin "2") (pinfunction "2_2") (pintype "passive"))
      (node (ref "C157") (pin "2") (pinfunction "2_2") (pintype "passive"))
      (node (ref "C158") (pin "2") (pinfunction "2_2") (pintype "passive"))
      (node (ref "C159") (pin "2") (pinfunction "2_2") (pintype "passive"))
      (node (ref "U8") (pin "K19") (pinfunction "BIGCPU_VDD_12_K19") (pintype "passive"))
      (node (ref "U8") (pin "K21") (pinfunction "BIGCPU_VDD_13_K21") (pintype "passive"))
      (node (ref "U8") (pin "L18") (pinfunction "BIGCPU_VDD_8_L18") (pintype "passive"))
      (node (ref "U8") (pin "L19") (pinfunction "BIGCPU_VDD_1_L19") (pintype "passive"))
      (node (ref "U8") (pin "L21") (pinfunction "BIGCPU_VDD_2_L21") (pintype "passive"))
      (node (ref "U8") (pin "L23") (pinfunction "BIGCPU_VDD_11_L23") (pintype "passive"))
      (node (ref "U8") (pin "M18") (pinfunction "BIGCPU_VDD_3_M18") (pintype "passive"))
      (node (ref "U8") (pin "M19") (pinfunction "BIGCPU_VDD_4_M19") (pintype "passive"))
      (node (ref "U8") (pin "M20") (pinfunction "BIGCPU_VDD_5_M20") (pintype "passive"))
      (node (ref "U8") (pin "M21") (pinfunction "BIGCPU_VDD_6_M21") (pintype "passive"))
      (node (ref "U8") (pin "M22") (pinfunction "BIGCPU_VDD_7_M22") (pintype "passive"))
      (node (ref "U8") (pin "N20") (pinfunction "BIGCPU_VDD_10_N20") (pintype "passive"))
      (node (ref "U8") (pin "N22") (pinfunction "BIGCPU_VDD_9_N22") (pintype "passive"))
    )
    (net (code "4") (name "VCC_CPU_L") (class "Default")
      (node (ref "C116") (pin "2") (pinfunction "2_2") (pintype "passive"))
      (node (ref "C118") (pin "2") (pinfunction "2_2") (pintype "passive"))
      (node (ref "C122") (pin "2") (pinfunction "2_2") (pintype "passive"))
      (node (ref "C123") (pin "2") (pinfunction "2_2") (pintype "passive"))
      (node (ref "C124") (pin "2") (pinfunction "2_2") (pintype "passive"))
      (node (ref "C125") (pin "2") (pinfunction "2_2") (pintype "passive"))
      (node (ref "C126") (pin "2") (pinfunction "2_2") (pintype "passive"))
      (node (ref "U8") (pin "P20") (pinfunction "LITCPU_VDD_1_P20") (pintype "passive"))
      (node (ref "U8") (pin "P22") (pinfunction "LITCPU_VDD_4_P22") (pintype "passive"))
      (node (ref "U8") (pin "R19") (pinfunction "LITCPU_VDD_2_R19") (pintype "passive"))
      (node (ref "U8") (pin "R20") (pinfunction "LITCPU_VDD_3_R20") (pintype "passive"))
      (node (ref "U8") (pin "R22") (pinfunction "LITCPU_VDD_7_R22") (pintype "passive"))
      (node (ref "U8") (pin "T20") (pinfunction "LITCPU_VDD_6_T20") (pintype "passive"))
      (node (ref "U8") (pin "T22") (pinfunction "LITCPU_VDD_5_T22") (pintype "passive"))
    )
    (net (code "5") (name "VCC_GPU") (class "Default")
      (node (ref "C127") (pin "2") (pinfunction "2_2") (pintype "passive"))
      (node (ref "C128") (pin "2") (pinfunction "2_2") (pintype "passive"))
      (node (ref "C129") (pin "2") (pinfunction "2_2") (pintype "passive"))
      (node (ref "C130") (pin "2") (pinfunction "2_2") (pintype "passive"))
      (node (ref "C131") (pin "2") (pinfunction "2_2") (pintype "passive"))
      (node (ref "C132") (pin "2") (pinfunction "2_2") (pintype "passive"))
      (node (ref "C133") (pin "2") (pinfunction "2_2") (pintype "passive"))
      (node (ref "C134") (pin "2") (pinfunction "2_2") (pintype "passive"))
      (node (ref "C135") (pin "2") (pinfunction "2_2") (pintype "passive"))
      (node (ref "C136") (pin "2") (pinfunction "2_2") (pintype "passive"))
      (node (ref "C137") (pin "2") (pinfunction "2_2") (pintype "passive"))
      (node (ref "U8") (pin "R11") (pinfunction "GPU_VDD_8_R11") (pintype "passive"))
      (node (ref "U8") (pin "R12") (pinfunction "GPU_VDD_9_R12") (pintype "passive"))
      (node (ref "U8") (pin "R13") (pinfunction "GPU_VDD_13_R13") (pintype "passive"))
      (node (ref "U8") (pin "T11") (pinfunction "GPU_VDD_10_T11") (pintype "passive"))
      (node (ref "U8") (pin "T12") (pinfunction "GPU_VDD_11_T12") (pintype "passive"))
      (node (ref "U8") (pin "T13") (pinfunction "GPU_VDD_12_T13") (pintype "passive"))
      (node (ref "U8") (pin "T14") (pinfunction "GPU_VDD_14_T14") (pintype "passive"))
      (node (ref "U8") (pin "U13") (pinfunction "GPU_VDD_7_U13") (pintype "passive"))
      (node (ref "U8") (pin "V11") (pinfunction "GPU_VDD_15_V11") (pintype "passive"))
      (node (ref "U8") (pin "V12") (pinfunction "GPU_VDD_16_V12") (pintype "passive"))
      (node (ref "U8") (pin "V13") (pinfunction "GPU_VDD_6_V13") (pintype "passive"))
      (node (ref "U8") (pin "V14") (pinfunction "GPU_VDD_5_V14") (pintype "passive"))
      (node (ref "U8") (pin "V15") (pinfunction "GPU_VDD_4_V15") (pintype "passive"))
      (node (ref "U8") (pin "V16") (pinfunction "GPU_VDD_17_V16") (pintype "passive"))
      (node (ref "U8") (pin "W10") (pinfunction "GPU_VDD_20_W10") (pintype "passive"))
      (node (ref "U8") (pin "W11") (pinfunction "GPU_VDD_1_W11") (pintype "passive"))
      (node (ref "U8") (pin "W12") (pinfunction "GPU_VDD_2_W12") (pintype "passive"))
      (node (ref "U8") (pin "W14") (pinfunction "GPU_VDD_3_W14") (pintype "passive"))
      (node (ref "U8") (pin "W15") (pinfunction "GPU_VDD_19_W15") (pintype "passive"))
      (node (ref "U8") (pin "W16") (pinfunction "GPU_VDD_18_W16") (pintype "passive"))
    )
    (net (code "6") (name "VCC_LOG") (class "Default")
      (node (ref "C138") (pin "2") (pinfunction "2_2") (pintype "passive"))
      (node (ref "C139") (pin "2") (pinfunction "2_2") (pintype "passive"))
      (node (ref "C140") (pin "2") (pinfunction "2_2") (pintype "passive"))
      (node (ref "C141") (pin "2") (pinfunction "2_2") (pintype "passive"))
      (node (ref "C142") (pin "2") (pinfunction "2_2") (pintype "passive"))
      (node (ref "C143") (pin "2") (pinfunction "2_2") (pintype "passive"))
      (node (ref "C144") (pin "2") (pinfunction "2_2") (pintype "passive"))
      (node (ref "C145") (pin "2") (pinfunction "2_2") (pintype "passive"))
      (node (ref "U8") (pin "L17") (pinfunction "LOGIC_VDD_10_L17") (pintype "passive"))
      (node (ref "U8") (pin "M17") (pinfunction "LOGIC_VDD_9_M17") (pintype "passive"))
      (node (ref "U8") (pin "T17") (pinfunction "LOGIC_VDD_11_T17") (pintype "passive"))
      (node (ref "U8") (pin "U17") (pinfunction "LOGIC_VDD_8_U17") (pintype "passive"))
      (node (ref "U8") (pin "U18") (pinfunction "LOGIC_VDD_7_U18") (pintype "passive"))
      (node (ref "U8") (pin "U20") (pinfunction "LOGIC_VDD_12_U20") (pintype "passive"))
      (node (ref "U8") (pin "V18") (pinfunction "LOGIC_VDD_5_V18") (pintype "passive"))
      (node (ref "U8") (pin "V19") (pinfunction "LOGIC_VDD_4_V19") (pintype "passive"))
      (node (ref "U8") (pin "V20") (pinfunction "LOGIC_VDD_3_V20") (pintype "passive"))
      (node (ref "U8") (pin "V21") (pinfunction "LOGIC_VDD_2_V21") (pintype "passive"))
      (node (ref "U8") (pin "V22") (pinfunction "LOGIC_VDD_1_V22") (pintype "passive"))
      (node (ref "U8") (pin "W20") (pinfunction "LOGIC_VDD_6_W20") (pintype "passive"))
    )
    (net (code "7") (name "VDD_CPU_B_FB") (class "Default")
      (node (ref "U8") (pin "N18") (pinfunction "BIGCPU_VDD_COM_N18") (pintype "passive"))
    )
    (net (code "8") (name "VDD_GPU_FB") (class "Default")
      (node (ref "U8") (pin "T15") (pinfunction "GPU_VDD_COM_T15") (pintype "passive"))
    )
  )
)
